# Display.net
KiCad netlist of a schematic drawn in Altium Designer
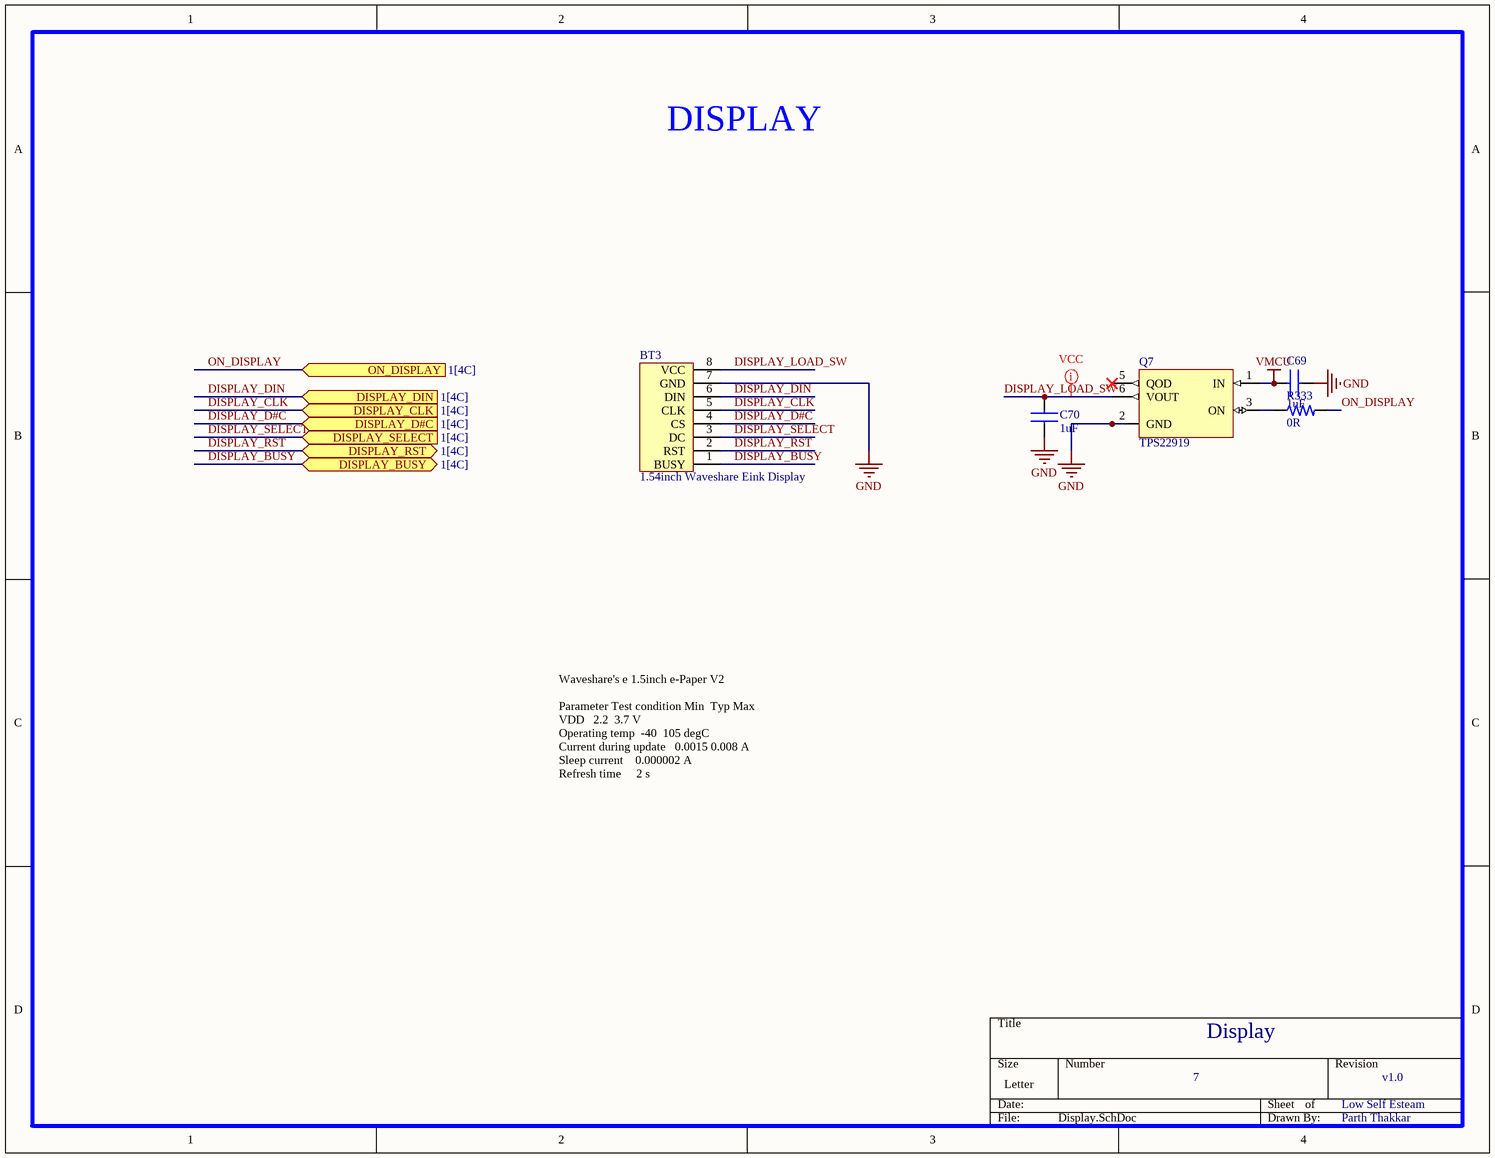
[diagram p0: Display.SchDoc]

(export (version "E")
  (design (tool "Eeschema 10.0.6"))
  (components
    (comp (ref "BT3")
      (value "1.54inch Waveshare Eink Display")
      (footprint "1.54inch waveshare eink")
      (libsource (lib "Keyboard_parts") (part "1.54inch Waveshare Eink Display"))
    )
    (comp (ref "C69")
      (value "1uF")
      (footprint "Capacitor 0603")
      (fields
        (field (name "MANUFACTURER") "Murata")
        (field (name "MANUFACTURER PART NUMBER") "GRM188R61A105KA61D")
        (field (name "Comment") "CAP 1uF 10V 0603")
      )
      (libsource (lib "Keyboard_parts") (part "CAP 1uF 10V 0603"))
    )
    (comp (ref "C70")
      (value "1uF")
      (footprint "CAPACITOR 0805")
      (description "Multilayer Ceramic Capacitor, 1 uF, 10 V, ± 20%, X5R, 0201 [0603 Metric]")
      (fields
        (field (name "MANUFACTURER") "Murata")
        (field (name "MANUFACTURER PART NUMBER") "GRM033R61A105ME15D")
      )
      (libsource (lib "Keyboard_parts") (part "CAP 47uF 10V 0805"))
    )
    (comp (ref "Q7")
      (value "TPS22919")
      (footprint "TPS22919DCKR - Load SW")
      (description "Buffer/Inverter Based Peripheral Driver, 3A, PDSO6")
      (fields
        (field (name "MANUFACTURER") "Texas Instruments")
        (field (name "MANUFACTURER PART NUMBER") "TPS22919DCKR")
      )
      (libsource (lib "Keyboard_parts") (part "TPS22919"))
    )
    (comp (ref "R333")
      (value "0R")
      (footprint "Resistor 0402")
      (description "Metal Glaze/thick Film, 0.0625W, 0ohm, Surface Mount, 0402")
      (fields
        (field (name "MANUFACTURER") "Yageo")
        (field (name "MANUFACTURER PART NUMBER") "RC0402JR-070RL")
      )
      (libsource (lib "Keyboard_parts") (part "RES 0R 0402"))
    )
  )
  (nets
    (net (code "1") (name "/DISPLAY_BUSY") (class "Default")
      (node (ref "BT3") (pin "1") (pinfunction "BUSY_1") (pintype "passive"))
    )
    (net (code "2") (name "/DISPLAY_CLK") (class "Default")
      (node (ref "BT3") (pin "5") (pinfunction "CLK_5") (pintype "passive"))
    )
    (net (code "3") (name "/DISPLAY_D#C") (class "Default")
      (node (ref "BT3") (pin "4") (pinfunction "CS_4") (pintype "passive"))
    )
    (net (code "4") (name "/DISPLAY_DIN") (class "Default")
      (node (ref "BT3") (pin "6") (pinfunction "DIN_6") (pintype "passive"))
    )
    (net (code "5") (name "/DISPLAY_LOAD_SW") (class "Default")
      (node (ref "BT3") (pin "8") (pinfunction "VCC_8") (pintype "passive"))
      (node (ref "C70") (pin "1") (pinfunction "1_1") (pintype "passive"))
      (node (ref "Q7") (pin "6") (pinfunction "VOUT_6") (pintype "output"))
    )
    (net (code "6") (name "/DISPLAY_RST") (class "Default")
      (node (ref "BT3") (pin "2") (pinfunction "RST_2") (pintype "passive"))
    )
    (net (code "7") (name "/DISPLAY_SELECT") (class "Default")
      (node (ref "BT3") (pin "3") (pinfunction "DC_3") (pintype "passive"))
    )
    (net (code "8") (name "/ON_DISPLAY") (class "Default")
      (node (ref "R333") (pin "2") (pinfunction "2_2") (pintype "passive"))
    )
    (net (code "9") (name "GND") (class "Default")
      (node (ref "BT3") (pin "7") (pinfunction "GND_7") (pintype "passive"))
      (node (ref "C69") (pin "2") (pinfunction "2_2") (pintype "passive"))
      (node (ref "C70") (pin "2") (pinfunction "2_2") (pintype "passive"))
      (node (ref "Q7") (pin "2") (pinfunction "GND_2") (pintype "power_in"))
    )
    (net (code "10") (name "Net-(Q7-ON)") (class "Default")
      (node (ref "Q7") (pin "3") (pinfunction "ON_3") (pintype "bidirectional"))
      (node (ref "R333") (pin "1") (pinfunction "1_1") (pintype "passive"))
    )
    (net (code "11") (name "VMCU") (class "Default")
      (node (ref "C69") (pin "1") (pinfunction "1_1") (pintype "passive"))
      (node (ref "Q7") (pin "1") (pinfunction "IN_1") (pintype "input"))
    )
    (net (code "12") (name "unconnected-(Q7-QOD-Pad5)") (class "Default")
      (node (ref "Q7") (pin "5") (pinfunction "QOD_5") (pintype "output+no_connect"))
    )
  )
)
